# Top.net
KiCad netlist of a schematic drawn in Altium Designer
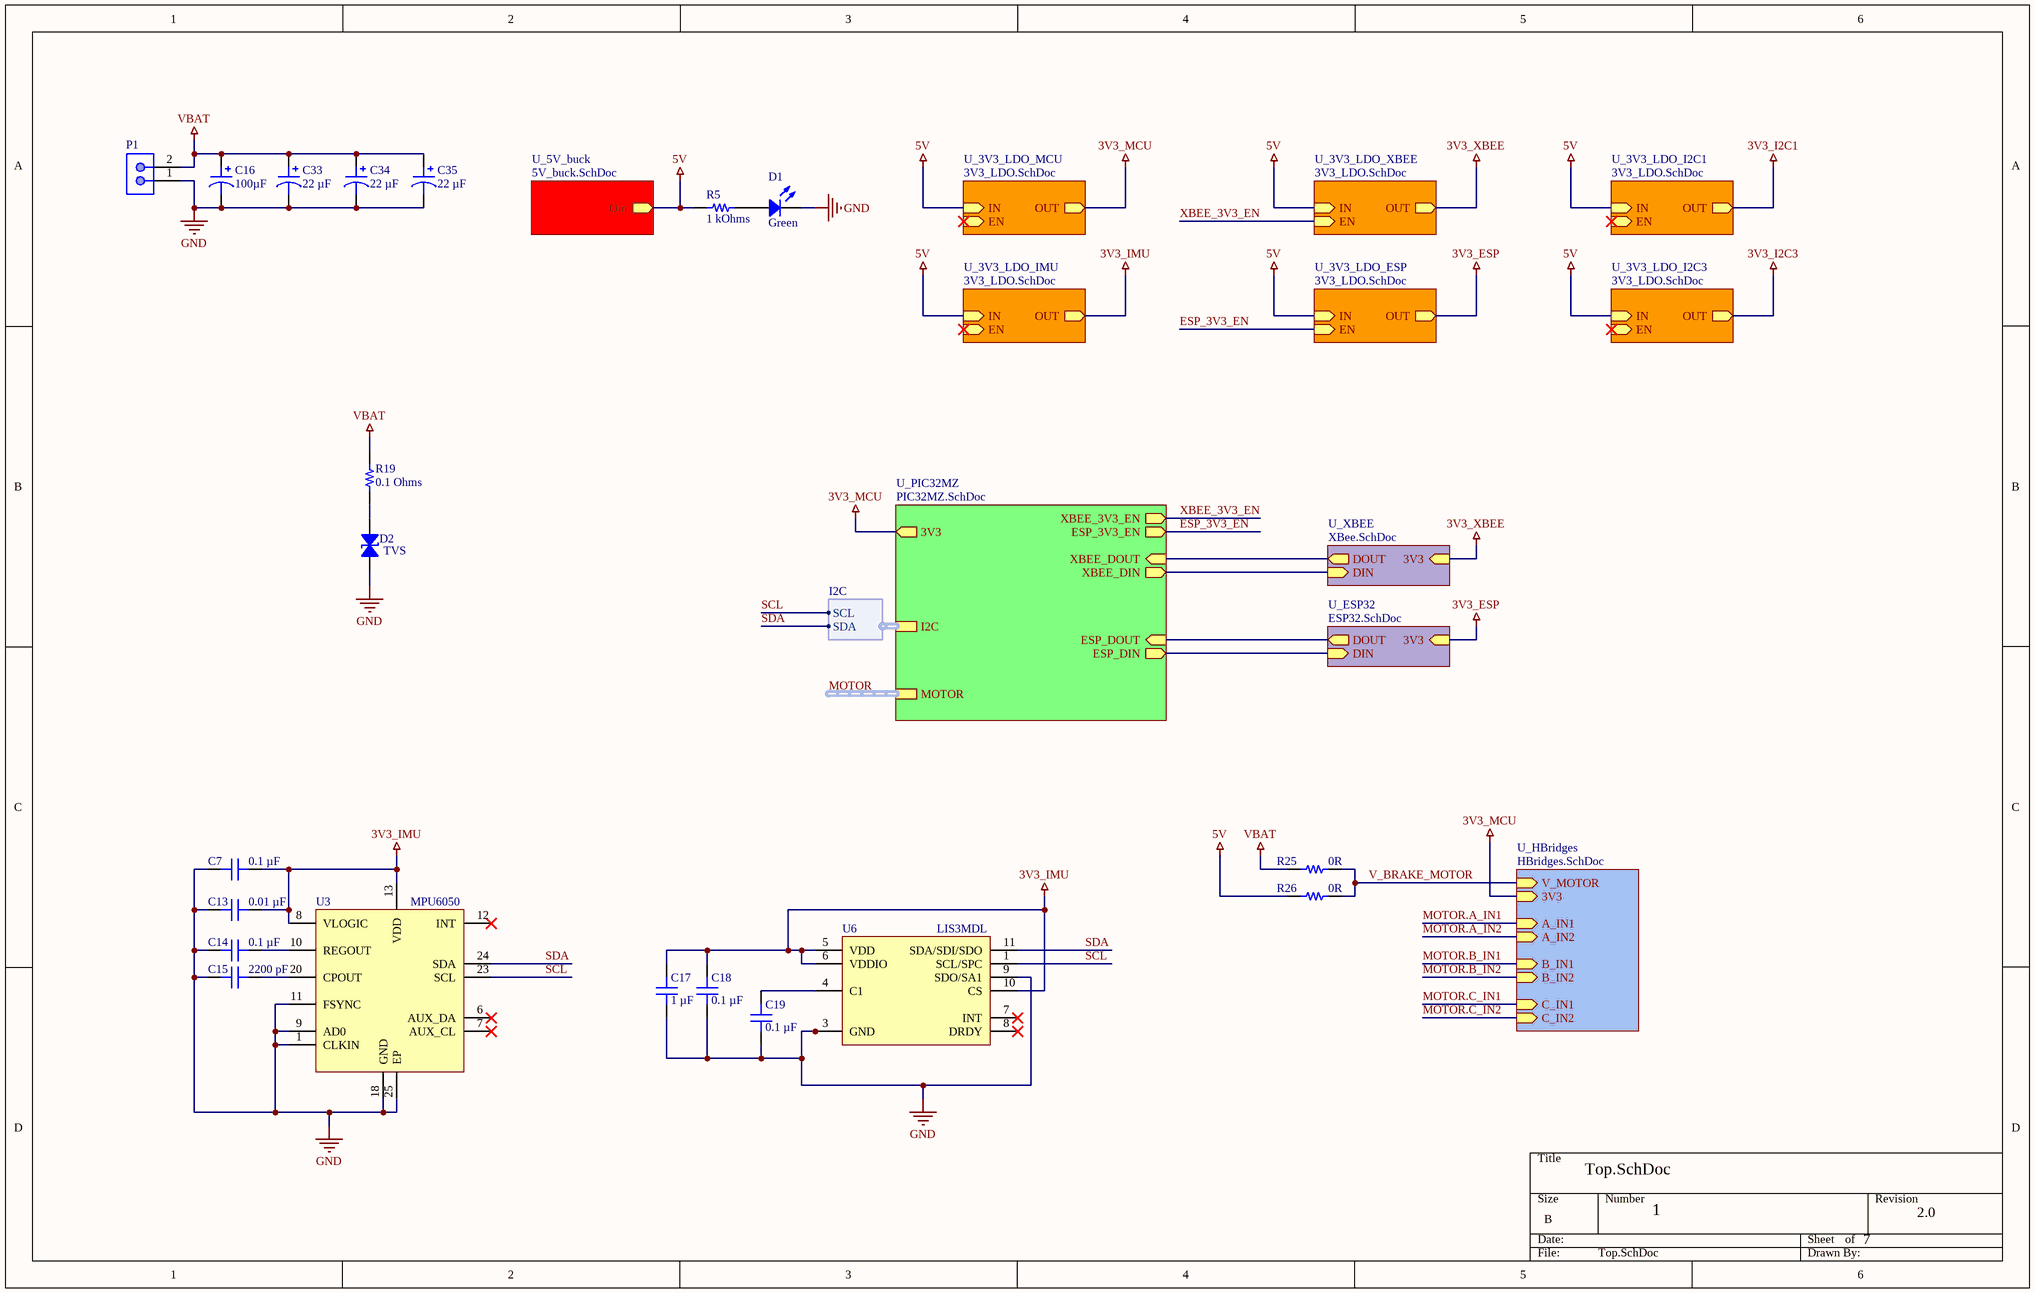
[diagram p0: Top.SchDoc]

(export (version "E")
  (design (tool "Eeschema 10.0.6"))
  (components
    (comp (ref "C7")
      (value "0.1 µF")
      (footprint "CAP 0402_1005")
      (description "CAP CER 0.1UF 16V X7R 0402")
      (fields (field (name "PART NUMBER") "C0402C104K4RACAUTO") (field (name "MANUFACTURER") "KEMET"))
      (libsource (lib "Celestial Altium Library - altium_library") (part "Capacitor"))
    )
    (comp (ref "C13")
      (value "0.01 µF")
      (footprint "CAP 0402_1005")
      (description "CAP CER 0.1UF 16V X7R 0402")
      (fields (field (name "PART NUMBER") "C0402C104K4RACAUTO") (field (name "MANUFACTURER") "KEMET"))
      (libsource (lib "Celestial Altium Library - altium_library") (part "Capacitor"))
    )
    (comp (ref "C14")
      (value "0.1 µF")
      (footprint "CAP 0402_1005")
      (description "CAP CER 0.1UF 16V X7R 0402")
      (fields (field (name "PART NUMBER") "C0402C104K4RACAUTO") (field (name "MANUFACTURER") "KEMET"))
      (libsource (lib "Celestial Altium Library - altium_library") (part "Capacitor"))
    )
    (comp (ref "C15")
      (value "2200 pF")
      (footprint "CAP 0402_1005")
      (description "CAP CER 0.1UF 16V X7R 0402")
      (fields (field (name "PART NUMBER") "C0402C104K4RACAUTO") (field (name "MANUFACTURER") "KEMET"))
      (libsource (lib "Celestial Altium Library - altium_library") (part "Capacitor"))
    )
    (comp (ref "C16")
      (value "100µF")
      (footprint "CAP POL 2917_7343")
      (description "CAP TANT 100UF 20% 20V 2917")
      (fields (field (name "PART NUMBER") "293D107X0020E2TE3") (field (name "MANUFACTURER") "Vishay Sprague"))
      (libsource (lib "Celestial Altium Library - altium_library") (part "Polarised Capacitor"))
    )
    (comp (ref "C17")
      (value "1 µF")
      (footprint "CAP 0402_1005")
      (description "CAP CER 0.1UF 16V X7R 0402")
      (fields (field (name "PART NUMBER") "C0402C104K4RACAUTO") (field (name "MANUFACTURER") "KEMET"))
      (libsource (lib "Celestial Altium Library - altium_library") (part "Capacitor"))
    )
    (comp (ref "C18")
      (value "0.1 µF")
      (footprint "CAP 0402_1005")
      (description "CAP CER 0.1UF 16V X7R 0402")
      (fields (field (name "PART NUMBER") "C0402C104K4RACAUTO") (field (name "MANUFACTURER") "KEMET"))
      (libsource (lib "Celestial Altium Library - altium_library") (part "Capacitor"))
    )
    (comp (ref "C19")
      (value "0.1 µF")
      (footprint "CAP 0402_1005")
      (description "CAP CER 0.1UF 16V X7R 0402")
      (fields (field (name "PART NUMBER") "C0402C104K4RACAUTO") (field (name "MANUFACTURER") "KEMET"))
      (libsource (lib "Celestial Altium Library - altium_library") (part "Capacitor"))
    )
    (comp (ref "C33")
      (value "22 µF")
      (footprint "CAP ALSMD 5.3MM H5.4MM")
      (description "CAP ALUM 22UF 20% 35V SMD")
      (fields
        (field (name "PART NUMBER") "EMZA350ADA220ME61G")
        (field (name "MANUFACTURER") "United Chemi-Con")
      )
      (libsource (lib "Celestial Altium Library - altium_library") (part "Polarised Capacitor"))
    )
    (comp (ref "C34")
      (value "22 µF")
      (footprint "CAP ALSMD 5.3MM H5.4MM")
      (description "CAP ALUM 22UF 20% 35V SMD")
      (fields
        (field (name "PART NUMBER") "EMZA350ADA220ME61G")
        (field (name "MANUFACTURER") "United Chemi-Con")
      )
      (libsource (lib "Celestial Altium Library - altium_library") (part "Polarised Capacitor"))
    )
    (comp (ref "C35")
      (value "22 µF")
      (footprint "CAP ALSMD 5.3MM H5.4MM")
      (description "CAP ALUM 22UF 20% 35V SMD")
      (fields
        (field (name "PART NUMBER") "EMZA350ADA220ME61G")
        (field (name "MANUFACTURER") "United Chemi-Con")
      )
      (libsource (lib "Celestial Altium Library - altium_library") (part "Polarised Capacitor"))
    )
    (comp (ref "D1")
      (value "Green")
      (footprint "LED 0603_1608 GREEN")
      (description "1.6X0.8MM LC GREEN PIXSOLED DOME")
      (fields (field (name "PART NUMBER") "XZCDGK53W-8VF") (field (name "MANUFACTURER") "SunLED"))
      (libsource (lib "Celestial Altium Library - altium_library") (part "LED"))
    )
    (comp (ref "D2")
      (value "TVS")
      (footprint "DO214AC SMA")
      (description "TVS DIODE 110V 177V DO214AC")
      (fields
        (field (name "PART NUMBER") "SMAJ110CA-E3/61")
        (field (name "MANUFACTURER") "Vishay Semiconductor Diodes Division")
      )
      (libsource (lib "Celestial Altium Library - altium_library") (part "Diode TVS"))
    )
    (comp (ref "P1")
      (value "2 pin 2mm JST Male")
      (footprint "2pin - 2mm JST male")
      (libsource (lib "IC") (part "2 pin 2mm JST Male"))
    )
    (comp (ref "R5")
      (value "1 kOhms")
      (footprint "YAGEO RES 0402_1005")
      (description "RES 1K OHM 1% 1/16W 0402")
      (fields (field (name "PART NUMBER") "RC0402FR-071KL") (field (name "MANUFACTURER") "Yageo"))
      (libsource (lib "Celestial Altium Library - altium_library") (part "Resistor"))
    )
    (comp (ref "R19")
      (value "0.1 Ohms")
      (footprint "RES 1206_3216")
      (description "RES 0 OHM JUMPER 1206")
      (fields (field (name "PART NUMBER") "WSL120600000ZEA9") (field (name "MANUFACTURER") "Vishay Dale"))
      (libsource (lib "Celestial Altium Library - altium_library") (part "Resistor"))
    )
    (comp (ref "R25")
      (value "0R")
      (footprint "RES 0603_1608")
      (description "2T WSTC0603 0.33W 100PPM 4 MOHM")
      (fields
        (field (name "PART NUMBER") "WSTC0603RLR004FNR")
        (field (name "MANUFACTURER") "Littelfuse Inc.")
      )
      (libsource (lib "Celestial Altium Library - altium_library") (part "Resistor"))
    )
    (comp (ref "R26")
      (value "0R")
      (footprint "RES 0603_1608")
      (description "2T WSTC0603 0.33W 100PPM 4 MOHM")
      (fields
        (field (name "PART NUMBER") "WSTC0603RLR004FNR")
        (field (name "MANUFACTURER") "Littelfuse Inc.")
      )
      (libsource (lib "Celestial Altium Library - altium_library") (part "Resistor"))
    )
    (comp (ref "U3") (value "MPU6050") (footprint "IC_MPU6050") (libsource (lib "IC") (part "MPU6050")))
    (comp (ref "U6")
      (value "LIS3MDL")
      (footprint "LGA12_ST")
      (description "Magnetometer")
      (libsource (lib "IC") (part "LIS3MDL"))
    )
  )
  (nets
    (net (code "17") (name "/SCL") (class "Default")
      (node (ref "U3") (pin "23") (pinfunction "SCL_23") (pintype "passive"))
      (node (ref "U6") (pin "1") (pinfunction "SCL/SPC_1") (pintype "passive"))
    )
    (net (code "18") (name "/SDA") (class "Default")
      (node (ref "U3") (pin "24") (pinfunction "SDA_24") (pintype "passive"))
      (node (ref "U6") (pin "11") (pinfunction "SDA/SDI/SDO_11") (pintype "passive"))
    )
    (net (code "19") (name "/V_BRAKE_MOTOR") (class "Default")
      (node (ref "R25") (pin "2") (pinfunction "2_2") (pintype "passive"))
      (node (ref "R26") (pin "2") (pinfunction "2_2") (pintype "passive"))
    )
    (net (code "27") (name "3V3_IMU") (class "Default")
      (node (ref "C13") (pin "1") (pinfunction "1_1") (pintype "passive"))
      (node (ref "C17") (pin "1") (pinfunction "1_1") (pintype "passive"))
      (node (ref "C18") (pin "1") (pinfunction "1_1") (pintype "passive"))
      (node (ref "C7") (pin "1") (pinfunction "1_1") (pintype "passive"))
      (node (ref "U3") (pin "13") (pinfunction "VDD_13") (pintype "passive"))
      (node (ref "U3") (pin "8") (pinfunction "VLOGIC_8") (pintype "passive"))
      (node (ref "U6") (pin "10") (pinfunction "CS_10") (pintype "passive"))
      (node (ref "U6") (pin "5") (pinfunction "VDD_5") (pintype "passive"))
      (node (ref "U6") (pin "6") (pinfunction "VDDIO_6") (pintype "passive"))
    )
    (net (code "30") (name "5V") (class "Default")
      (node (ref "R26") (pin "1") (pinfunction "1_1") (pintype "passive"))
      (node (ref "R5") (pin "1") (pinfunction "1_1") (pintype "passive"))
    )
    (net (code "31") (name "GND") (class "Default")
      (node (ref "C13") (pin "2") (pinfunction "2_2") (pintype "passive"))
      (node (ref "C14") (pin "2") (pinfunction "2_2") (pintype "passive"))
      (node (ref "C15") (pin "2") (pinfunction "2_2") (pintype "passive"))
      (node (ref "C16") (pin "2") (pinfunction "2_2") (pintype "passive"))
      (node (ref "C17") (pin "2") (pinfunction "2_2") (pintype "passive"))
      (node (ref "C18") (pin "2") (pinfunction "2_2") (pintype "passive"))
      (node (ref "C19") (pin "2") (pinfunction "2_2") (pintype "passive"))
      (node (ref "C33") (pin "2") (pinfunction "2_2") (pintype "passive"))
      (node (ref "C34") (pin "2") (pinfunction "2_2") (pintype "passive"))
      (node (ref "C35") (pin "2") (pinfunction "2_2") (pintype "passive"))
      (node (ref "C7") (pin "2") (pinfunction "2_2") (pintype "passive"))
      (node (ref "D1") (pin "2") (pinfunction "2_2") (pintype "passive"))
      (node (ref "D2") (pin "2") (pinfunction "2_2") (pintype "passive"))
      (node (ref "P1") (pin "1") (pinfunction "1_1") (pintype "passive"))
      (node (ref "U3") (pin "1") (pinfunction "CLKIN_1") (pintype "passive"))
      (node (ref "U3") (pin "11") (pinfunction "FSYNC_11") (pintype "passive"))
      (node (ref "U3") (pin "18") (pinfunction "GND_18") (pintype "passive"))
      (node (ref "U3") (pin "25") (pinfunction "EP_25") (pintype "passive"))
      (node (ref "U3") (pin "9") (pinfunction "AD0_9") (pintype "passive"))
      (node (ref "U6") (pin "12") (pinfunction "Reserved_12") (pintype "passive"))
      (node (ref "U6") (pin "2") (pinfunction "Reserved_2") (pintype "passive"))
      (node (ref "U6") (pin "3") (pinfunction "GND_3") (pintype "passive"))
      (node (ref "U6") (pin "9") (pinfunction "SDO/SA1_9") (pintype "passive"))
    )
    (net (code "32") (name "Net-(D1-Pad1)") (class "Default")
      (node (ref "D1") (pin "1") (pinfunction "1_1") (pintype "passive"))
      (node (ref "R5") (pin "2") (pinfunction "2_2") (pintype "passive"))
    )
    (net (code "33") (name "Net-(D2-Pad1)") (class "Default")
      (node (ref "D2") (pin "1") (pinfunction "1_1") (pintype "passive"))
      (node (ref "R19") (pin "1") (pinfunction "1_1") (pintype "passive"))
    )
    (net (code "34") (name "Net-(U3-CPOUT)") (class "Default")
      (node (ref "C15") (pin "1") (pinfunction "1_1") (pintype "passive"))
      (node (ref "U3") (pin "20") (pinfunction "CPOUT_20") (pintype "passive"))
    )
    (net (code "35") (name "Net-(U3-REGOUT)") (class "Default")
      (node (ref "C14") (pin "1") (pinfunction "1_1") (pintype "passive"))
      (node (ref "U3") (pin "10") (pinfunction "REGOUT_10") (pintype "passive"))
    )
    (net (code "36") (name "Net-(U6-C1)") (class "Default")
      (node (ref "C19") (pin "1") (pinfunction "1_1") (pintype "passive"))
      (node (ref "U6") (pin "4") (pinfunction "C1_4") (pintype "passive"))
    )
    (net (code "37") (name "VBAT") (class "Default")
      (node (ref "C16") (pin "1") (pinfunction "1_1") (pintype "passive"))
      (node (ref "C33") (pin "1") (pinfunction "1_1") (pintype "passive"))
      (node (ref "C34") (pin "1") (pinfunction "1_1") (pintype "passive"))
      (node (ref "C35") (pin "1") (pinfunction "1_1") (pintype "passive"))
      (node (ref "P1") (pin "2") (pinfunction "2_2") (pintype "passive"))
      (node (ref "R19") (pin "2") (pinfunction "2_2") (pintype "passive"))
      (node (ref "R25") (pin "1") (pinfunction "1_1") (pintype "passive"))
    )
    (net (code "38") (name "unconnected-(U3-AUX_CL-Pad7)") (class "Default")
      (node (ref "U3") (pin "7") (pinfunction "AUX_CL_7") (pintype "passive+no_connect"))
    )
    (net (code "39") (name "unconnected-(U3-AUX_DA-Pad6)") (class "Default")
      (node (ref "U3") (pin "6") (pinfunction "AUX_DA_6") (pintype "passive+no_connect"))
    )
    (net (code "40") (name "unconnected-(U3-INT-Pad12)") (class "Default")
      (node (ref "U3") (pin "12") (pinfunction "INT_12") (pintype "passive+no_connect"))
    )
    (net (code "41") (name "unconnected-(U6-DRDY-Pad8)") (class "Default")
      (node (ref "U6") (pin "8") (pinfunction "DRDY_8") (pintype "passive+no_connect"))
    )
    (net (code "42") (name "unconnected-(U6-INT-Pad7)") (class "Default")
      (node (ref "U6") (pin "7") (pinfunction "INT_7") (pintype "passive+no_connect"))
    )
  )
)
